# xover.net
KiCad netlist of a schematic drawn in EAGLE
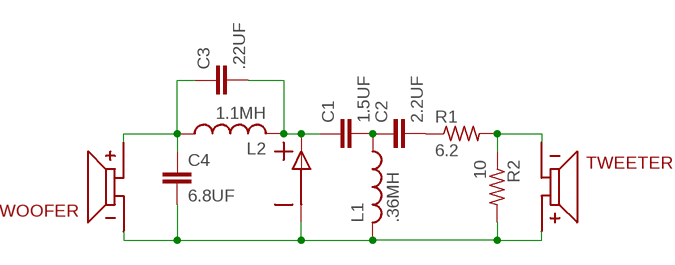
[diagram p0: schematic, sheet 1]

(export (version "E")
  (design (tool "Eeschema 10.0.6"))
  (components
    (comp (ref "C1")
      (value "1.5UF")
      (footprint "eagle-import:1.5UF")
      (libsource (lib "eagle-import") (part "1.5UF"))
    )
    (comp (ref "C2")
      (value "2.2UF")
      (footprint "eagle-import:2.2UF")
      (libsource (lib "eagle-import") (part "2.2UF"))
    )
    (comp (ref "C3")
      (value ".22UF")
      (footprint "eagle-import:.22UF")
      (libsource (lib "eagle-import") (part ".22UF"))
    )
    (comp (ref "C4")
      (value "6.8UF")
      (footprint "eagle-import:6.8UF")
      (libsource (lib "eagle-import") (part "6.8UF"))
    )
    (comp (ref "INPUT")
      (value "INPUTREV")
      (footprint "eagle-import:SCREW")
      (libsource (lib "eagle-import") (part "INPUTREV"))
    )
    (comp (ref "L1")
      (value ".36MH")
      (footprint "eagle-import:.36VERT")
      (libsource (lib "eagle-import") (part ".36MHVERTREV"))
    )
    (comp (ref "L2")
      (value "1.1MH")
      (footprint "eagle-import:1.1MH")
      (libsource (lib "eagle-import") (part "1.1MHREV"))
    )
    (comp (ref "R1")
      (value "6.2")
      (footprint "eagle-import:6.2")
      (libsource (lib "eagle-import") (part "6.2"))
    )
    (comp (ref "R2")
      (value "10")
      (footprint "eagle-import:6.2")
      (libsource (lib "eagle-import") (part "6.210"))
    )
    (comp (ref "TWEETER")
      (value "TWEETER")
      (footprint "eagle-import:SCREW")
      (libsource (lib "eagle-import") (part "TWEETER"))
    )
    (comp (ref "WOOFER")
      (value "TWEETER")
      (footprint "eagle-import:SCREW")
      (libsource (lib "eagle-import") (part "TWEETER"))
    )
  )
  (nets
    (net (code "1") (name "Net-(C1-1)") (class "Default")
      (node (ref "C1") (pin "P$1") (pinfunction "1_P$1") (pintype "passive"))
      (node (ref "C3") (pin "P$2") (pinfunction "2_P$2") (pintype "passive"))
      (node (ref "INPUT") (pin "P$1") (pinfunction "PLUS_P$1") (pintype "bidirectional"))
      (node (ref "L2") (pin "P$1") (pinfunction "2_P$1") (pintype "passive"))
    )
    (net (code "2") (name "Net-(C1-2)") (class "Default")
      (node (ref "C1") (pin "P$2") (pinfunction "2_P$2") (pintype "passive"))
      (node (ref "C2") (pin "P$1") (pinfunction "1_P$1") (pintype "passive"))
      (node (ref "L1") (pin "P$2") (pinfunction "1_P$2") (pintype "passive"))
    )
    (net (code "3") (name "Net-(C2-2)") (class "Default")
      (node (ref "C2") (pin "P$2") (pinfunction "2_P$2") (pintype "passive"))
      (node (ref "R1") (pin "P$1") (pinfunction "1_P$1") (pintype "passive"))
    )
    (net (code "4") (name "Net-(C3-1)") (class "Default")
      (node (ref "C3") (pin "P$1") (pinfunction "1_P$1") (pintype "passive"))
      (node (ref "C4") (pin "P$1") (pinfunction "1_P$1") (pintype "passive"))
      (node (ref "L2") (pin "P$2") (pinfunction "1_P$2") (pintype "passive"))
      (node (ref "WOOFER") (pin "P$2") (pinfunction "PLUS_P$2") (pintype "bidirectional"))
    )
    (net (code "5") (name "Net-(C4-2)") (class "Default")
      (node (ref "C4") (pin "P$2") (pinfunction "2_P$2") (pintype "passive"))
      (node (ref "INPUT") (pin "P$2") (pinfunction "MINUS_P$2") (pintype "bidirectional"))
      (node (ref "L1") (pin "P$1") (pinfunction "2_P$1") (pintype "passive"))
      (node (ref "R2") (pin "P$2") (pinfunction "2_P$2") (pintype "passive"))
      (node (ref "TWEETER") (pin "P$2") (pinfunction "PLUS_P$2") (pintype "bidirectional"))
      (node (ref "WOOFER") (pin "P$1") (pinfunction "MINUS_P$1") (pintype "bidirectional"))
    )
    (net (code "6") (name "Net-(R1-2)") (class "Default")
      (node (ref "R1") (pin "P$2") (pinfunction "2_P$2") (pintype "passive"))
      (node (ref "R2") (pin "P$1") (pinfunction "1_P$1") (pintype "passive"))
      (node (ref "TWEETER") (pin "P$1") (pinfunction "MINUS_P$1") (pintype "bidirectional"))
    )
  )
)
